# BNC_CONECTOR.net
KiCad netlist of a schematic drawn in EAGLE
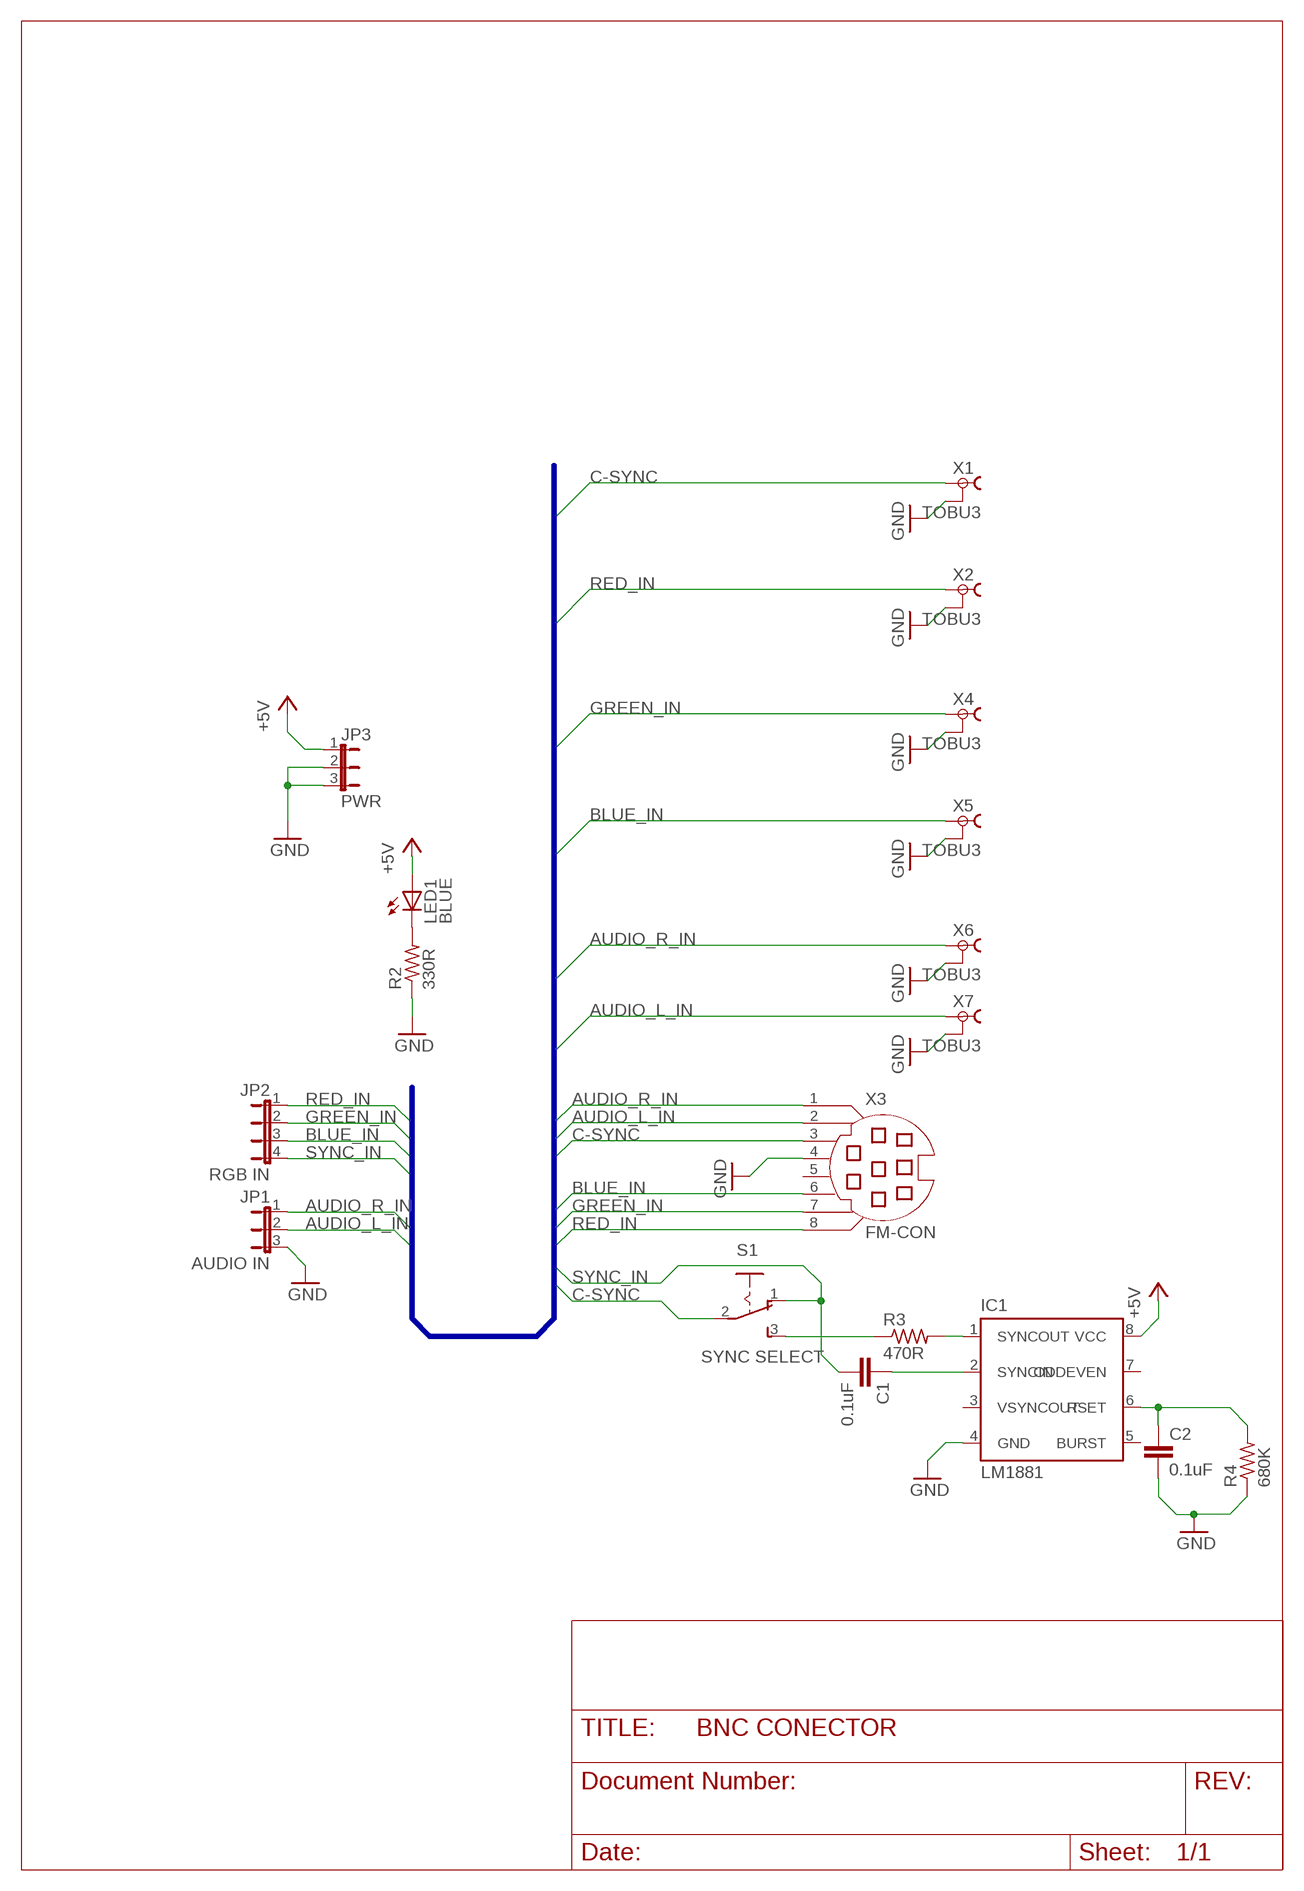
[diagram p0: schematic, sheet 1]

(export (version "E")
  (design (tool "Eeschema 10.0.6"))
  (components
    (comp (ref "C1")
      (value "0.1uF")
      (footprint "eagle-import:C7.5B3")
      (libsource (lib "eagle-import") (part "C7.5/3"))
    )
    (comp (ref "C2")
      (value "0.1uF")
      (footprint "eagle-import:C7.5B3")
      (libsource (lib "eagle-import") (part "C7.5/3"))
    )
    (comp (ref "IC1")
      (value "LM1881")
      (footprint "eagle-import:DIL08")
      (libsource (lib "eagle-import") (part "LM1881"))
    )
    (comp (ref "JP1")
      (value "AUDIO IN")
      (footprint "eagle-import:JP2")
      (libsource (lib "eagle-import") (part "JP2E"))
    )
    (comp (ref "JP2")
      (value "RGB IN")
      (footprint "eagle-import:JP4")
      (libsource (lib "eagle-import") (part "JP4E"))
    )
    (comp (ref "JP3")
      (value "PWR")
      (footprint "eagle-import:JP2")
      (libsource (lib "eagle-import") (part "JP2E"))
    )
    (comp (ref "LED1")
      (value "BLUE")
      (footprint "eagle-import:LED5MM")
      (libsource (lib "eagle-import") (part "LED5MM"))
    )
    (comp (ref "R2")
      (value "330R")
      (footprint "eagle-import:0204_7")
      (libsource (lib "eagle-import") (part "R-US_0204/7"))
    )
    (comp (ref "R3")
      (value "470R")
      (footprint "eagle-import:0204_7")
      (libsource (lib "eagle-import") (part "R-US_0204/7"))
    )
    (comp (ref "R4")
      (value "680K")
      (footprint "eagle-import:0204_7")
      (libsource (lib "eagle-import") (part "R-US_0204/7"))
    )
    (comp (ref "S1")
      (value "SYNC SELECT")
      (footprint "eagle-import:255SB")
      (libsource (lib "eagle-import") (part "255SB"))
    )
    (comp (ref "X1")
      (value "TOBU3")
      (footprint "eagle-import:TOBU3")
      (fields (field (name "MF") "FARNELL") (field (name "MPN") "TOBU 3"))
      (libsource (lib "eagle-import") (part "TOBU3"))
    )
    (comp (ref "X2")
      (value "TOBU3")
      (footprint "eagle-import:TOBU3")
      (fields (field (name "MF") "FARNELL") (field (name "MPN") "TOBU 3"))
      (libsource (lib "eagle-import") (part "TOBU3"))
    )
    (comp (ref "X3")
      (value "FM-CON")
      (footprint "eagle-import:MDIN08SS")
      (libsource (lib "eagle-import") (part "MD08SS"))
    )
    (comp (ref "X4")
      (value "TOBU3")
      (footprint "eagle-import:TOBU3")
      (fields (field (name "MF") "FARNELL") (field (name "MPN") "TOBU 3"))
      (libsource (lib "eagle-import") (part "TOBU3"))
    )
    (comp (ref "X5")
      (value "TOBU3")
      (footprint "eagle-import:TOBU3")
      (fields (field (name "MF") "FARNELL") (field (name "MPN") "TOBU 3"))
      (libsource (lib "eagle-import") (part "TOBU3"))
    )
    (comp (ref "X6")
      (value "TOBU3")
      (footprint "eagle-import:TOBU3")
      (fields (field (name "MF") "FARNELL") (field (name "MPN") "TOBU 3"))
      (libsource (lib "eagle-import") (part "TOBU3"))
    )
    (comp (ref "X7")
      (value "TOBU3")
      (footprint "eagle-import:TOBU3")
      (fields (field (name "MF") "FARNELL") (field (name "MPN") "TOBU 3"))
      (libsource (lib "eagle-import") (part "TOBU3"))
    )
  )
  (nets
    (net (code "1") (name "+5V") (class "Default")
      (node (ref "IC1") (pin "8") (pinfunction "VCC_8") (pintype "power_in"))
      (node (ref "JP3") (pin "1") (pinfunction "1_1") (pintype "passive"))
      (node (ref "LED1") (pin "A") (pinfunction "A_A") (pintype "passive"))
    )
    (net (code "2") (name "/AUDIO_L_IN") (class "Default")
      (node (ref "JP1") (pin "2") (pinfunction "2_2") (pintype "passive"))
      (node (ref "X3") (pin "2") (pinfunction "2_2") (pintype "passive"))
      (node (ref "X7") (pin "1") (pinfunction "1_1") (pintype "passive"))
    )
    (net (code "3") (name "/AUDIO_R_IN") (class "Default")
      (node (ref "JP1") (pin "1") (pinfunction "1_1") (pintype "passive"))
      (node (ref "X3") (pin "1") (pinfunction "1_1") (pintype "passive"))
      (node (ref "X6") (pin "1") (pinfunction "1_1") (pintype "passive"))
    )
    (net (code "4") (name "/BLUE_IN") (class "Default")
      (node (ref "JP2") (pin "3") (pinfunction "3_3") (pintype "passive"))
      (node (ref "X3") (pin "6") (pinfunction "6_6") (pintype "passive"))
      (node (ref "X5") (pin "1") (pinfunction "1_1") (pintype "passive"))
    )
    (net (code "5") (name "/C-SYNC") (class "Default")
      (node (ref "S1") (pin "2") (pinfunction "P_2") (pintype "passive"))
      (node (ref "X1") (pin "1") (pinfunction "1_1") (pintype "passive"))
      (node (ref "X3") (pin "3") (pinfunction "3_3") (pintype "passive"))
    )
    (net (code "6") (name "/GREEN_IN") (class "Default")
      (node (ref "JP2") (pin "2") (pinfunction "2_2") (pintype "passive"))
      (node (ref "X3") (pin "7") (pinfunction "7_7") (pintype "passive"))
      (node (ref "X4") (pin "1") (pinfunction "1_1") (pintype "passive"))
    )
    (net (code "7") (name "/RED_IN") (class "Default")
      (node (ref "JP2") (pin "1") (pinfunction "1_1") (pintype "passive"))
      (node (ref "X2") (pin "1") (pinfunction "1_1") (pintype "passive"))
      (node (ref "X3") (pin "8") (pinfunction "8_8") (pintype "passive"))
    )
    (net (code "8") (name "/SYNC_IN") (class "Default")
      (node (ref "C1") (pin "2") (pinfunction "2_2") (pintype "passive"))
      (node (ref "JP2") (pin "4") (pinfunction "4_4") (pintype "passive"))
      (node (ref "S1") (pin "1") (pinfunction "O_1") (pintype "passive"))
    )
    (net (code "9") (name "GND") (class "Default")
      (node (ref "C2") (pin "2") (pinfunction "2_2") (pintype "passive"))
      (node (ref "IC1") (pin "4") (pinfunction "GND_4") (pintype "power_in"))
      (node (ref "JP1") (pin "3") (pinfunction "3_3") (pintype "passive"))
      (node (ref "JP3") (pin "2") (pinfunction "2_2") (pintype "passive"))
      (node (ref "JP3") (pin "3") (pinfunction "3_3") (pintype "passive"))
      (node (ref "R2") (pin "1") (pinfunction "1_1") (pintype "passive"))
      (node (ref "R4") (pin "1") (pinfunction "1_1") (pintype "passive"))
      (node (ref "X1") (pin "2") (pinfunction "2_2") (pintype "passive"))
      (node (ref "X1") (pin "2@1") (pinfunction "2_2@1") (pintype "passive"))
      (node (ref "X1") (pin "2@2") (pinfunction "2_2@2") (pintype "passive"))
      (node (ref "X2") (pin "2") (pinfunction "2_2") (pintype "passive"))
      (node (ref "X2") (pin "2@1") (pinfunction "2_2@1") (pintype "passive"))
      (node (ref "X2") (pin "2@2") (pinfunction "2_2@2") (pintype "passive"))
      (node (ref "X3") (pin "4") (pinfunction "4_4") (pintype "passive"))
      (node (ref "X4") (pin "2") (pinfunction "2_2") (pintype "passive"))
      (node (ref "X4") (pin "2@1") (pinfunction "2_2@1") (pintype "passive"))
      (node (ref "X4") (pin "2@2") (pinfunction "2_2@2") (pintype "passive"))
      (node (ref "X5") (pin "2") (pinfunction "2_2") (pintype "passive"))
      (node (ref "X5") (pin "2@1") (pinfunction "2_2@1") (pintype "passive"))
      (node (ref "X5") (pin "2@2") (pinfunction "2_2@2") (pintype "passive"))
      (node (ref "X6") (pin "2") (pinfunction "2_2") (pintype "passive"))
      (node (ref "X6") (pin "2@1") (pinfunction "2_2@1") (pintype "passive"))
      (node (ref "X6") (pin "2@2") (pinfunction "2_2@2") (pintype "passive"))
      (node (ref "X7") (pin "2") (pinfunction "2_2") (pintype "passive"))
      (node (ref "X7") (pin "2@1") (pinfunction "2_2@1") (pintype "passive"))
      (node (ref "X7") (pin "2@2") (pinfunction "2_2@2") (pintype "passive"))
    )
    (net (code "10") (name "Net-(IC1-RSET)") (class "Default")
      (node (ref "C2") (pin "1") (pinfunction "1_1") (pintype "passive"))
      (node (ref "IC1") (pin "6") (pinfunction "RSET_6") (pintype "output"))
      (node (ref "R4") (pin "2") (pinfunction "2_2") (pintype "passive"))
    )
    (net (code "11") (name "Net-(IC1-SYNCIN)") (class "Default")
      (node (ref "C1") (pin "1") (pinfunction "1_1") (pintype "passive"))
      (node (ref "IC1") (pin "2") (pinfunction "SYNCIN_2") (pintype "input"))
    )
    (net (code "12") (name "Net-(IC1-SYNCOUT)") (class "Default")
      (node (ref "IC1") (pin "1") (pinfunction "SYNCOUT_1") (pintype "output"))
      (node (ref "R3") (pin "2") (pinfunction "2_2") (pintype "passive"))
    )
    (net (code "13") (name "Net-(LED1-C)") (class "Default")
      (node (ref "LED1") (pin "K") (pinfunction "C_K") (pintype "passive"))
      (node (ref "R2") (pin "2") (pinfunction "2_2") (pintype "passive"))
    )
    (net (code "14") (name "Net-(S1-S)") (class "Default")
      (node (ref "R3") (pin "1") (pinfunction "1_1") (pintype "passive"))
      (node (ref "S1") (pin "3") (pinfunction "S_3") (pintype "passive"))
    )
    (net (code "15") (name "unconnected-(IC1-BURST-Pad5)") (class "Default")
      (node (ref "IC1") (pin "5") (pinfunction "BURST_5") (pintype "output"))
    )
    (net (code "16") (name "unconnected-(IC1-ODDEVEN-Pad7)") (class "Default")
      (node (ref "IC1") (pin "7") (pinfunction "ODDEVEN_7") (pintype "output"))
    )
    (net (code "17") (name "unconnected-(IC1-VSYNCOUT-Pad3)") (class "Default")
      (node (ref "IC1") (pin "3") (pinfunction "VSYNCOUT_3") (pintype "output"))
    )
    (net (code "18") (name "unconnected-(X3-Pad5)") (class "Default")
      (node (ref "X3") (pin "5") (pinfunction "5_5") (pintype "passive"))
    )
  )
)
